# Microcontroller.net
KiCad netlist of a schematic drawn in Altium Designer
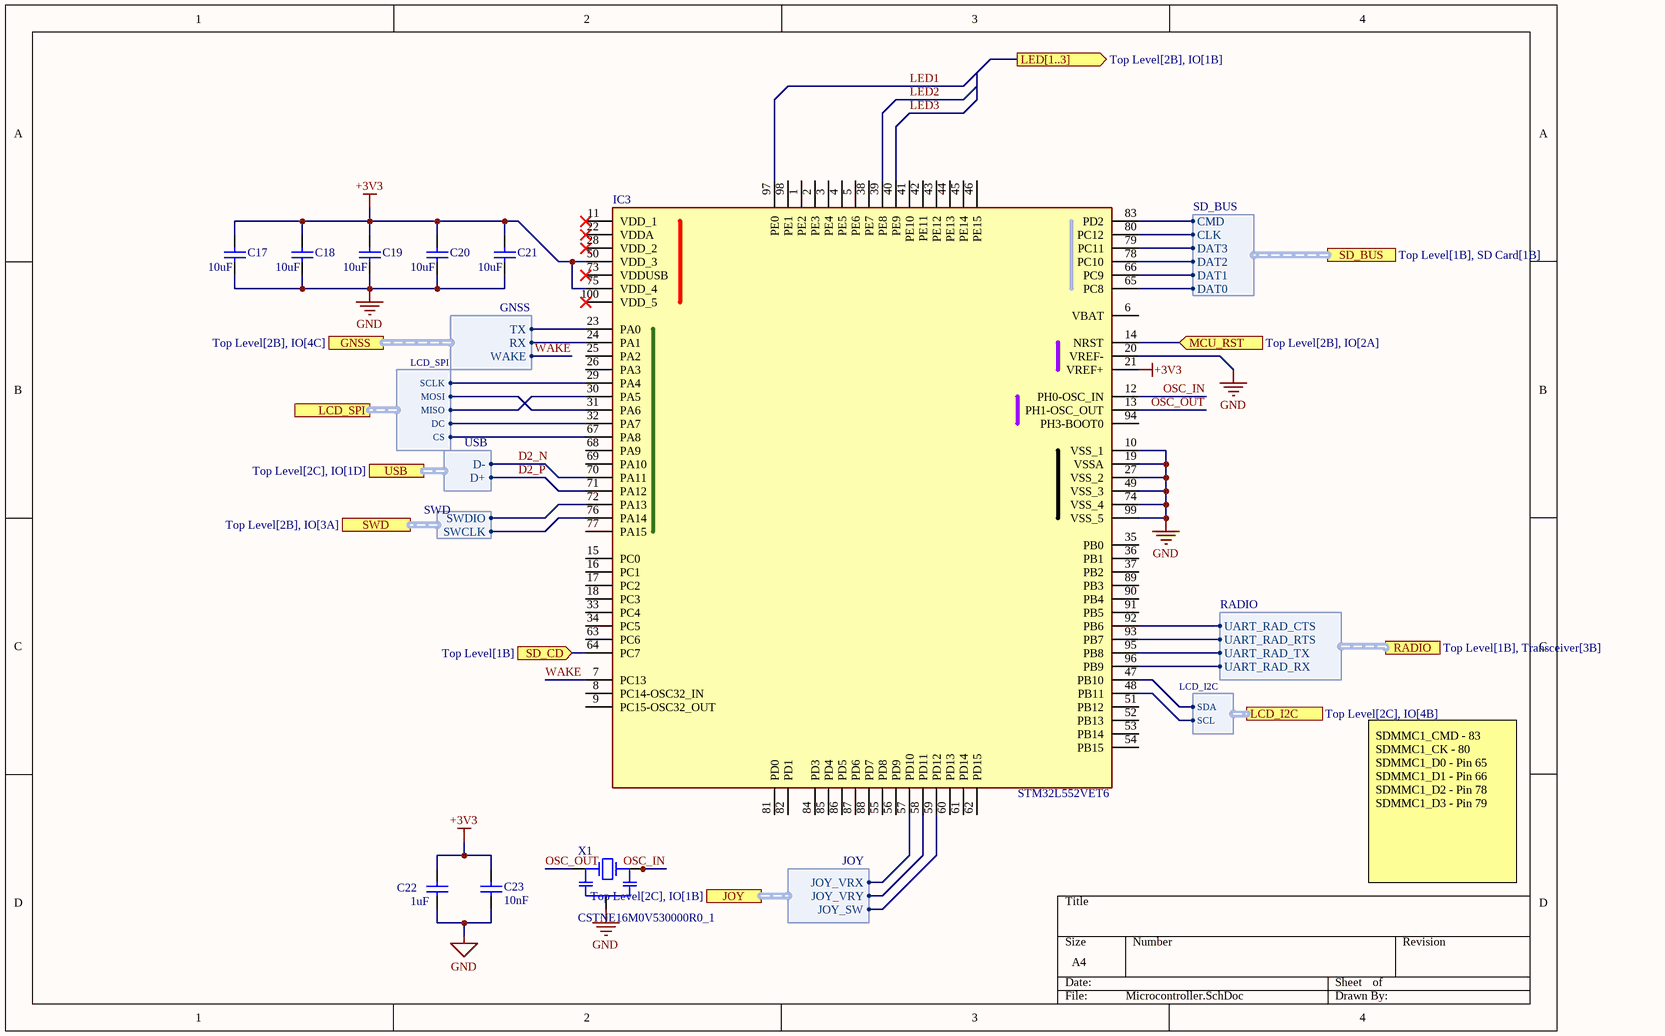
[diagram p0: Microcontroller.SchDoc]

(export (version "E")
  (design (tool "Eeschema 10.0.6"))
  (components
    (comp (ref "C17")
      (value "10uF")
      (footprint "CAPC2012X14N")
      (description "CAP CER 10UF 10V X5R 0805")
      (fields (field (name "VOLTAGE") "10V") (field (name "TOLERANCE") "10%"))
      (libsource (lib "Design 1 - Telemetry Module") (part "CMP-00046-3"))
    )
    (comp (ref "C18")
      (value "10uF")
      (footprint "CAPC2012X14N")
      (description "CAP CER 10UF 10V X5R 0805")
      (fields (field (name "VOLTAGE") "10V") (field (name "TOLERANCE") "10%"))
      (libsource (lib "Design 1 - Telemetry Module") (part "CMP-00046-3"))
    )
    (comp (ref "C19")
      (value "10uF")
      (footprint "CAPC2012X14N")
      (description "CAP CER 10UF 10V X5R 0805")
      (fields (field (name "VOLTAGE") "10V") (field (name "TOLERANCE") "10%"))
      (libsource (lib "Design 1 - Telemetry Module") (part "CMP-00046-3"))
    )
    (comp (ref "C20")
      (value "10uF")
      (footprint "CAPC2012X14N")
      (description "CAP CER 10UF 10V X5R 0805")
      (fields (field (name "VOLTAGE") "10V") (field (name "TOLERANCE") "10%"))
      (libsource (lib "Design 1 - Telemetry Module") (part "CMP-00046-3"))
    )
    (comp (ref "C21")
      (value "10uF")
      (footprint "CAPC2012X14N")
      (description "CAP CER 10UF 10V X5R 0805")
      (fields (field (name "VOLTAGE") "10V") (field (name "TOLERANCE") "10%"))
      (libsource (lib "Design 1 - Telemetry Module") (part "CMP-00046-3"))
    )
    (comp (ref "C22")
      (value "1uF")
      (footprint "CAPC1608X10N")
      (description "Cap Ceramic 1uF 10V X5R 10% SMD 0603 85°C Paper T/R")
      (fields (field (name "TOLERANCE") "10%") (field (name "VOLTAGE") "10V"))
      (libsource (lib "Receiver_Library") (part "C0603C105K8PACTU"))
    )
    (comp (ref "C23")
      (value "10nF")
      (footprint "CAPC1608X10N")
      (description "Cap Ceramic 0.01uF 50V X7R 5% SMD 0603 125C Paper T/R")
      (fields (field (name "TOLERANCE") "5%") (field (name "Comment") "C0603C103J5RACTU"))
      (libsource (lib "Receiver_Library") (part "CMP-00047-2"))
    )
    (comp (ref "IC3")
      (value "STM32L552VET6")
      (footprint "QFP50P1600X1600X160-100N")
      (description "Integrated Circuit")
      (fields (field (name "MOUSER PART NUMBER") "511-STM32L552VET6"))
      (libsource (lib "Receiver_Library") (part "STM32L552VET6"))
    )
    (comp (ref "X1")
      (value "CSTNE16M0V530000R0_1")
      (footprint "FP-CSTNE16M0V530000R0-MFG")
      (description "Resonators 16.0 MHZ 15PF")
      (fields
        (field (name "MANUFACTURER_PART_NUMBER") "CSTNE16M0V530000R0")
        (field (name "MOUSER PART NUMBER") "81-CSTNE16M0V530000R")
      )
      (libsource (lib "Receiver_Library") (part "CSTNE16M0V530000R0_1"))
    )
  )
  (nets
    (net (code "9") (name "+3V3") (class "Default")
      (node (ref "C17") (pin "2") (pinfunction "2_2") (pintype "passive"))
      (node (ref "C18") (pin "2") (pinfunction "2_2") (pintype "passive"))
      (node (ref "C19") (pin "2") (pinfunction "2_2") (pintype "passive"))
      (node (ref "C20") (pin "2") (pinfunction "2_2") (pintype "passive"))
      (node (ref "C21") (pin "2") (pinfunction "2_2") (pintype "passive"))
      (node (ref "C22") (pin "2") (pinfunction "2_2") (pintype "passive"))
      (node (ref "C23") (pin "2") (pinfunction "2_2") (pintype "passive"))
      (node (ref "IC3") (pin "21") (pinfunction "VREF+_21") (pintype "passive"))
      (node (ref "IC3") (pin "50") (pinfunction "VDD_3_50") (pintype "passive"))
      (node (ref "IC3") (pin "75") (pinfunction "VDD_4_75") (pintype "passive"))
    )
    (net (code "10") (name "/CLK") (class "Default")
      (node (ref "IC3") (pin "80") (pinfunction "PC12_80") (pintype "passive"))
    )
    (net (code "11") (name "/CMD") (class "Default")
      (node (ref "IC3") (pin "83") (pinfunction "PD2_83") (pintype "passive"))
    )
    (net (code "12") (name "/CS") (class "Default")
      (node (ref "IC3") (pin "67") (pinfunction "PA8_67") (pintype "passive"))
    )
    (net (code "13") (name "/D2_N") (class "Default")
      (node (ref "IC3") (pin "70") (pinfunction "PA11_70") (pintype "passive"))
    )
    (net (code "14") (name "/D2_P") (class "Default")
      (node (ref "IC3") (pin "71") (pinfunction "PA12_71") (pintype "passive"))
    )
    (net (code "15") (name "/DAT0") (class "Default")
      (node (ref "IC3") (pin "65") (pinfunction "PC8_65") (pintype "passive"))
    )
    (net (code "16") (name "/DAT1") (class "Default")
      (node (ref "IC3") (pin "66") (pinfunction "PC9_66") (pintype "passive"))
    )
    (net (code "17") (name "/DAT2") (class "Default")
      (node (ref "IC3") (pin "78") (pinfunction "PC10_78") (pintype "passive"))
    )
    (net (code "18") (name "/DAT3") (class "Default")
      (node (ref "IC3") (pin "79") (pinfunction "PC11_79") (pintype "passive"))
    )
    (net (code "19") (name "/DC") (class "Default")
      (node (ref "IC3") (pin "32") (pinfunction "PA7_32") (pintype "passive"))
    )
    (net (code "20") (name "/JOY_SW") (class "Default")
      (node (ref "IC3") (pin "59") (pinfunction "PD12_59") (pintype "passive"))
    )
    (net (code "21") (name "/JOY_VRX") (class "Default")
      (node (ref "IC3") (pin "57") (pinfunction "PD10_57") (pintype "passive"))
    )
    (net (code "22") (name "/JOY_VRY") (class "Default")
      (node (ref "IC3") (pin "58") (pinfunction "PD11_58") (pintype "passive"))
    )
    (net (code "23") (name "/LED1") (class "Default")
      (node (ref "IC3") (pin "97") (pinfunction "PE0_97") (pintype "passive"))
    )
    (net (code "24") (name "/LED2") (class "Default")
      (node (ref "IC3") (pin "39") (pinfunction "PE8_39") (pintype "passive"))
    )
    (net (code "25") (name "/LED3") (class "Default")
      (node (ref "IC3") (pin "40") (pinfunction "PE9_40") (pintype "passive"))
    )
    (net (code "27") (name "/MCU_RST") (class "Default")
      (node (ref "IC3") (pin "14") (pinfunction "NRST_14") (pintype "passive"))
    )
    (net (code "28") (name "/MISO") (class "Default")
      (node (ref "IC3") (pin "30") (pinfunction "PA5_30") (pintype "passive"))
    )
    (net (code "29") (name "/MOSI") (class "Default")
      (node (ref "IC3") (pin "31") (pinfunction "PA6_31") (pintype "passive"))
    )
    (net (code "30") (name "/OSC_IN") (class "Default")
      (node (ref "IC3") (pin "12") (pinfunction "PH0-OSC_IN_12") (pintype "passive"))
      (node (ref "X1") (pin "3") (pinfunction "OUT_3") (pintype "passive"))
    )
    (net (code "31") (name "/OSC_OUT") (class "Default")
      (node (ref "IC3") (pin "13") (pinfunction "PH1-OSC_OUT_13") (pintype "passive"))
      (node (ref "X1") (pin "1") (pinfunction "INPUT_1") (pintype "passive"))
    )
    (net (code "32") (name "/RX") (class "Default")
      (node (ref "IC3") (pin "24") (pinfunction "PA1_24") (pintype "passive"))
    )
    (net (code "33") (name "/SCL") (class "Default")
      (node (ref "IC3") (pin "48") (pinfunction "PB11_48") (pintype "passive"))
    )
    (net (code "34") (name "/SCLK") (class "Default")
      (node (ref "IC3") (pin "29") (pinfunction "PA4_29") (pintype "passive"))
    )
    (net (code "35") (name "/SDA") (class "Default")
      (node (ref "IC3") (pin "47") (pinfunction "PB10_47") (pintype "passive"))
    )
    (net (code "36") (name "/SD_CD") (class "Default")
      (node (ref "IC3") (pin "64") (pinfunction "PC7_64") (pintype "passive"))
    )
    (net (code "37") (name "/SWCLK") (class "Default")
      (node (ref "IC3") (pin "76") (pinfunction "PA14_76") (pintype "passive"))
    )
    (net (code "38") (name "/SWDIO") (class "Default")
      (node (ref "IC3") (pin "72") (pinfunction "PA13_72") (pintype "passive"))
    )
    (net (code "39") (name "/TX") (class "Default")
      (node (ref "IC3") (pin "23") (pinfunction "PA0_23") (pintype "passive"))
    )
    (net (code "40") (name "/UART_RAD_CTS") (class "Default")
      (node (ref "IC3") (pin "92") (pinfunction "PB6_92") (pintype "passive"))
    )
    (net (code "41") (name "/UART_RAD_RTS") (class "Default")
      (node (ref "IC3") (pin "93") (pinfunction "PB7_93") (pintype "passive"))
    )
    (net (code "42") (name "/UART_RAD_RX") (class "Default")
      (node (ref "IC3") (pin "96") (pinfunction "PB9_96") (pintype "passive"))
    )
    (net (code "43") (name "/UART_RAD_TX") (class "Default")
      (node (ref "IC3") (pin "95") (pinfunction "PB8_95") (pintype "passive"))
    )
    (net (code "44") (name "/WAKE") (class "Default")
      (node (ref "IC3") (pin "7") (pinfunction "PC13_7") (pintype "passive"))
    )
    (net (code "53") (name "GND") (class "Default")
      (node (ref "C17") (pin "1") (pinfunction "1_1") (pintype "passive"))
      (node (ref "C18") (pin "1") (pinfunction "1_1") (pintype "passive"))
      (node (ref "C19") (pin "1") (pinfunction "1_1") (pintype "passive"))
      (node (ref "C20") (pin "1") (pinfunction "1_1") (pintype "passive"))
      (node (ref "C21") (pin "1") (pinfunction "1_1") (pintype "passive"))
      (node (ref "C22") (pin "1") (pinfunction "1_1") (pintype "passive"))
      (node (ref "C23") (pin "1") (pinfunction "1_1") (pintype "passive"))
      (node (ref "IC3") (pin "10") (pinfunction "VSS_1_10") (pintype "passive"))
      (node (ref "IC3") (pin "19") (pinfunction "VSSA_19") (pintype "passive"))
      (node (ref "IC3") (pin "20") (pinfunction "VREF-_20") (pintype "passive"))
      (node (ref "IC3") (pin "27") (pinfunction "VSS_2_27") (pintype "passive"))
      (node (ref "IC3") (pin "49") (pinfunction "VSS_3_49") (pintype "passive"))
      (node (ref "IC3") (pin "74") (pinfunction "VSS_4_74") (pintype "passive"))
      (node (ref "IC3") (pin "99") (pinfunction "VSS_5_99") (pintype "passive"))
      (node (ref "X1") (pin "2") (pinfunction "GND_2") (pintype "passive"))
    )
    (net (code "54") (name "unconnected-(IC3-PA2-Pad25)") (class "Default")
      (node (ref "IC3") (pin "25") (pinfunction "PA2_25") (pintype "passive"))
    )
    (net (code "55") (name "unconnected-(IC3-PA3-Pad26)") (class "Default")
      (node (ref "IC3") (pin "26") (pinfunction "PA3_26") (pintype "passive"))
    )
    (net (code "56") (name "unconnected-(IC3-PA9-Pad68)") (class "Default")
      (node (ref "IC3") (pin "68") (pinfunction "PA9_68") (pintype "passive"))
    )
    (net (code "57") (name "unconnected-(IC3-PA10-Pad69)") (class "Default")
      (node (ref "IC3") (pin "69") (pinfunction "PA10_69") (pintype "passive"))
    )
    (net (code "58") (name "unconnected-(IC3-PA15-Pad77)") (class "Default")
      (node (ref "IC3") (pin "77") (pinfunction "PA15_77") (pintype "passive"))
    )
    (net (code "59") (name "unconnected-(IC3-PB0-Pad35)") (class "Default")
      (node (ref "IC3") (pin "35") (pinfunction "PB0_35") (pintype "passive"))
    )
    (net (code "60") (name "unconnected-(IC3-PB1-Pad36)") (class "Default")
      (node (ref "IC3") (pin "36") (pinfunction "PB1_36") (pintype "passive"))
    )
    (net (code "61") (name "unconnected-(IC3-PB2-Pad37)") (class "Default")
      (node (ref "IC3") (pin "37") (pinfunction "PB2_37") (pintype "passive"))
    )
    (net (code "62") (name "unconnected-(IC3-PB3-Pad89)") (class "Default")
      (node (ref "IC3") (pin "89") (pinfunction "PB3_89") (pintype "passive"))
    )
    (net (code "63") (name "unconnected-(IC3-PB4-Pad90)") (class "Default")
      (node (ref "IC3") (pin "90") (pinfunction "PB4_90") (pintype "passive"))
    )
    (net (code "64") (name "unconnected-(IC3-PB5-Pad91)") (class "Default")
      (node (ref "IC3") (pin "91") (pinfunction "PB5_91") (pintype "passive"))
    )
    (net (code "65") (name "unconnected-(IC3-PB12-Pad51)") (class "Default")
      (node (ref "IC3") (pin "51") (pinfunction "PB12_51") (pintype "passive"))
    )
    (net (code "66") (name "unconnected-(IC3-PB13-Pad52)") (class "Default")
      (node (ref "IC3") (pin "52") (pinfunction "PB13_52") (pintype "passive"))
    )
    (net (code "67") (name "unconnected-(IC3-PB14-Pad53)") (class "Default")
      (node (ref "IC3") (pin "53") (pinfunction "PB14_53") (pintype "passive"))
    )
    (net (code "68") (name "unconnected-(IC3-PB15-Pad54)") (class "Default")
      (node (ref "IC3") (pin "54") (pinfunction "PB15_54") (pintype "passive"))
    )
    (net (code "69") (name "unconnected-(IC3-PC0-Pad15)") (class "Default")
      (node (ref "IC3") (pin "15") (pinfunction "PC0_15") (pintype "passive"))
    )
    (net (code "70") (name "unconnected-(IC3-PC1-Pad16)") (class "Default")
      (node (ref "IC3") (pin "16") (pinfunction "PC1_16") (pintype "passive"))
    )
    (net (code "71") (name "unconnected-(IC3-PC2-Pad17)") (class "Default")
      (node (ref "IC3") (pin "17") (pinfunction "PC2_17") (pintype "passive"))
    )
    (net (code "72") (name "unconnected-(IC3-PC3-Pad18)") (class "Default")
      (node (ref "IC3") (pin "18") (pinfunction "PC3_18") (pintype "passive"))
    )
    (net (code "73") (name "unconnected-(IC3-PC4-Pad33)") (class "Default")
      (node (ref "IC3") (pin "33") (pinfunction "PC4_33") (pintype "passive"))
    )
    (net (code "74") (name "unconnected-(IC3-PC5-Pad34)") (class "Default")
      (node (ref "IC3") (pin "34") (pinfunction "PC5_34") (pintype "passive"))
    )
    (net (code "75") (name "unconnected-(IC3-PC6-Pad63)") (class "Default")
      (node (ref "IC3") (pin "63") (pinfunction "PC6_63") (pintype "passive"))
    )
    (net (code "76") (name "unconnected-(IC3-PC14-OSC32_IN-Pad8)") (class "Default")
      (node (ref "IC3") (pin "8") (pinfunction "PC14-OSC32_IN_8") (pintype "passive"))
    )
    (net (code "77") (name "unconnected-(IC3-PC15-OSC32_OUT-Pad9)") (class "Default")
      (node (ref "IC3") (pin "9") (pinfunction "PC15-OSC32_OUT_9") (pintype "passive"))
    )
    (net (code "78") (name "unconnected-(IC3-PD0-Pad81)") (class "Default")
      (node (ref "IC3") (pin "81") (pinfunction "PD0_81") (pintype "passive"))
    )
    (net (code "79") (name "unconnected-(IC3-PD1-Pad82)") (class "Default")
      (node (ref "IC3") (pin "82") (pinfunction "PD1_82") (pintype "passive"))
    )
    (net (code "80") (name "unconnected-(IC3-PD3-Pad84)") (class "Default")
      (node (ref "IC3") (pin "84") (pinfunction "PD3_84") (pintype "passive"))
    )
    (net (code "81") (name "unconnected-(IC3-PD4-Pad85)") (class "Default")
      (node (ref "IC3") (pin "85") (pinfunction "PD4_85") (pintype "passive"))
    )
    (net (code "82") (name "unconnected-(IC3-PD5-Pad86)") (class "Default")
      (node (ref "IC3") (pin "86") (pinfunction "PD5_86") (pintype "passive"))
    )
    (net (code "83") (name "unconnected-(IC3-PD6-Pad87)") (class "Default")
      (node (ref "IC3") (pin "87") (pinfunction "PD6_87") (pintype "passive"))
    )
    (net (code "84") (name "unconnected-(IC3-PD7-Pad88)") (class "Default")
      (node (ref "IC3") (pin "88") (pinfunction "PD7_88") (pintype "passive"))
    )
    (net (code "85") (name "unconnected-(IC3-PD8-Pad55)") (class "Default")
      (node (ref "IC3") (pin "55") (pinfunction "PD8_55") (pintype "passive"))
    )
    (net (code "86") (name "unconnected-(IC3-PD9-Pad56)") (class "Default")
      (node (ref "IC3") (pin "56") (pinfunction "PD9_56") (pintype "passive"))
    )
    (net (code "87") (name "unconnected-(IC3-PD13-Pad60)") (class "Default")
      (node (ref "IC3") (pin "60") (pinfunction "PD13_60") (pintype "passive"))
    )
    (net (code "88") (name "unconnected-(IC3-PD14-Pad61)") (class "Default")
      (node (ref "IC3") (pin "61") (pinfunction "PD14_61") (pintype "passive"))
    )
    (net (code "89") (name "unconnected-(IC3-PD15-Pad62)") (class "Default")
      (node (ref "IC3") (pin "62") (pinfunction "PD15_62") (pintype "passive"))
    )
    (net (code "90") (name "unconnected-(IC3-PE1-Pad98)") (class "Default")
      (node (ref "IC3") (pin "98") (pinfunction "PE1_98") (pintype "passive"))
    )
    (net (code "91") (name "unconnected-(IC3-PE2-Pad1)") (class "Default")
      (node (ref "IC3") (pin "1") (pinfunction "PE2_1") (pintype "passive"))
    )
    (net (code "92") (name "unconnected-(IC3-PE3-Pad2)") (class "Default")
      (node (ref "IC3") (pin "2") (pinfunction "PE3_2") (pintype "passive"))
    )
    (net (code "93") (name "unconnected-(IC3-PE4-Pad3)") (class "Default")
      (node (ref "IC3") (pin "3") (pinfunction "PE4_3") (pintype "passive"))
    )
    (net (code "94") (name "unconnected-(IC3-PE5-Pad4)") (class "Default")
      (node (ref "IC3") (pin "4") (pinfunction "PE5_4") (pintype "passive"))
    )
    (net (code "95") (name "unconnected-(IC3-PE6-Pad5)") (class "Default")
      (node (ref "IC3") (pin "5") (pinfunction "PE6_5") (pintype "passive"))
    )
    (net (code "96") (name "unconnected-(IC3-PE7-Pad38)") (class "Default")
      (node (ref "IC3") (pin "38") (pinfunction "PE7_38") (pintype "passive"))
    )
    (net (code "97") (name "unconnected-(IC3-PE10-Pad41)") (class "Default")
      (node (ref "IC3") (pin "41") (pinfunction "PE10_41") (pintype "passive"))
    )
    (net (code "98") (name "unconnected-(IC3-PE11-Pad42)") (class "Default")
      (node (ref "IC3") (pin "42") (pinfunction "PE11_42") (pintype "passive"))
    )
    (net (code "99") (name "unconnected-(IC3-PE12-Pad43)") (class "Default")
      (node (ref "IC3") (pin "43") (pinfunction "PE12_43") (pintype "passive"))
    )
    (net (code "100") (name "unconnected-(IC3-PE13-Pad44)") (class "Default")
      (node (ref "IC3") (pin "44") (pinfunction "PE13_44") (pintype "passive"))
    )
    (net (code "101") (name "unconnected-(IC3-PE14-Pad45)") (class "Default")
      (node (ref "IC3") (pin "45") (pinfunction "PE14_45") (pintype "passive"))
    )
    (net (code "102") (name "unconnected-(IC3-PE15-Pad46)") (class "Default")
      (node (ref "IC3") (pin "46") (pinfunction "PE15_46") (pintype "passive"))
    )
    (net (code "103") (name "unconnected-(IC3-PH3-BOOT0-Pad94)") (class "Default")
      (node (ref "IC3") (pin "94") (pinfunction "PH3-BOOT0_94") (pintype "passive"))
    )
    (net (code "104") (name "unconnected-(IC3-VBAT-Pad6)") (class "Default")
      (node (ref "IC3") (pin "6") (pinfunction "VBAT_6") (pintype "passive"))
    )
    (net (code "105") (name "unconnected-(IC3-VDDA-Pad22)") (class "Default")
      (node (ref "IC3") (pin "22") (pinfunction "VDDA_22") (pintype "passive+no_connect"))
    )
    (net (code "106") (name "unconnected-(IC3-VDDUSB-Pad73)") (class "Default")
      (node (ref "IC3") (pin "73") (pinfunction "VDDUSB_73") (pintype "passive+no_connect"))
    )
    (net (code "107") (name "unconnected-(IC3-VDD_1-Pad11)") (class "Default")
      (node (ref "IC3") (pin "11") (pinfunction "VDD_1_11") (pintype "passive+no_connect"))
    )
    (net (code "108") (name "unconnected-(IC3-VDD_2-Pad28)") (class "Default")
      (node (ref "IC3") (pin "28") (pinfunction "VDD_2_28") (pintype "passive+no_connect"))
    )
    (net (code "109") (name "unconnected-(IC3-VDD_5-Pad100)") (class "Default")
      (node (ref "IC3") (pin "100") (pinfunction "VDD_5_100") (pintype "passive+no_connect"))
    )
  )
)
